# Blinker_02.net
KiCad netlist of a schematic drawn in EAGLE
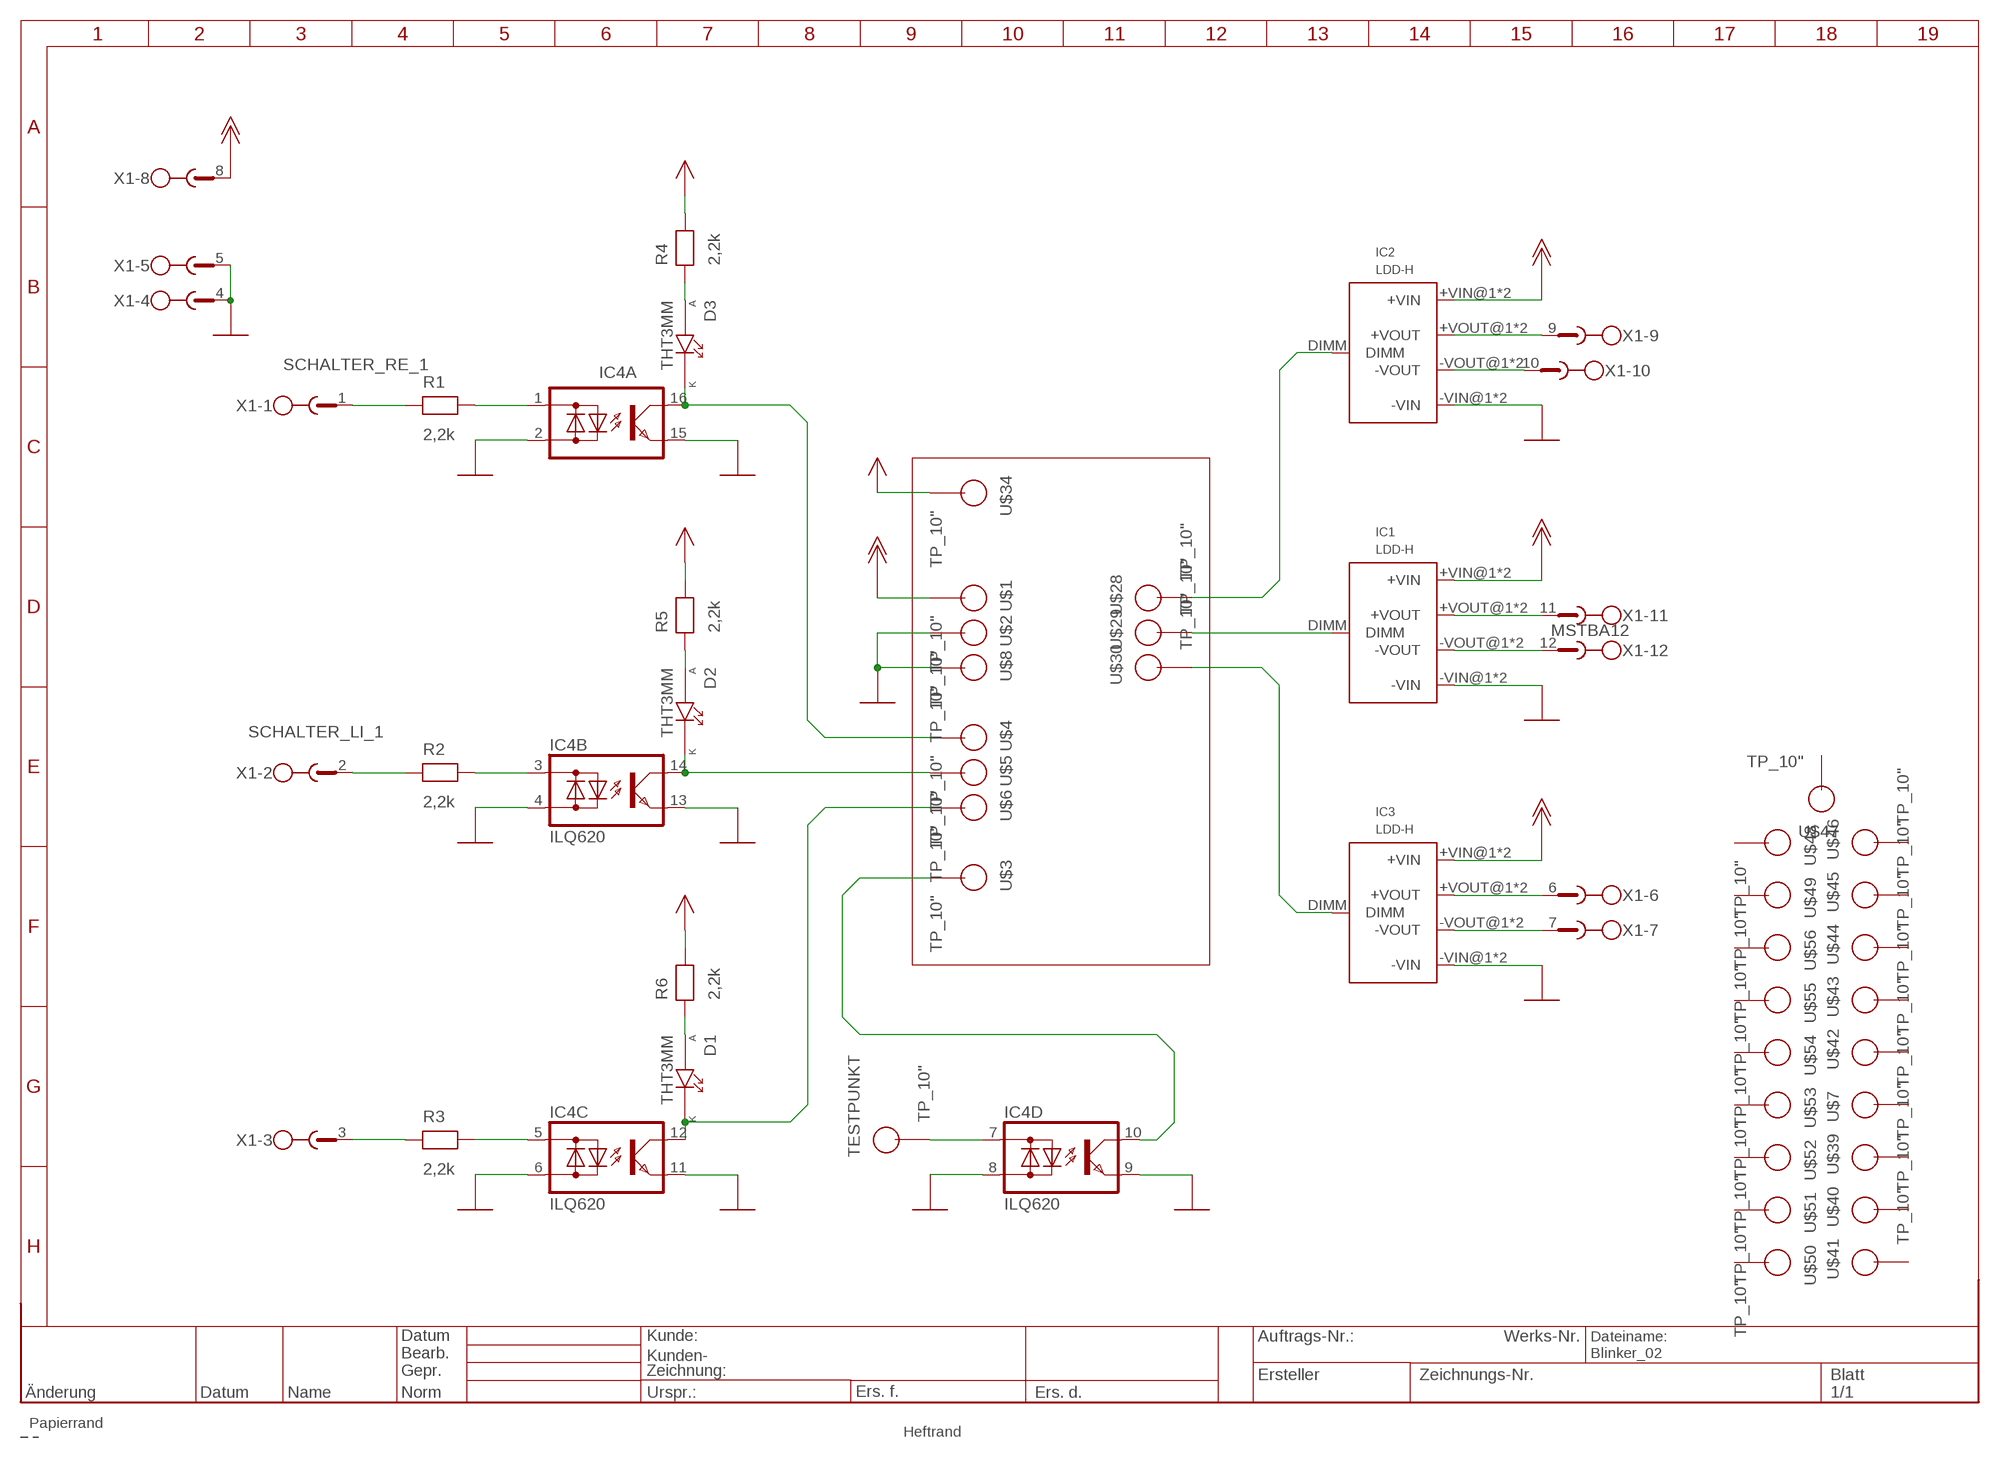
[diagram p0: schematic, sheet 1]

(export (version "E")
  (design (tool "Eeschema 10.0.6"))
  (components
    (comp (ref "D1")
      (value "THT3MM")
      (footprint "eagle-import:THT3MM")
      (libsource (lib "eagle-import") (part "THT3MM"))
    )
    (comp (ref "D2")
      (value "THT3MM")
      (footprint "eagle-import:THT3MM")
      (libsource (lib "eagle-import") (part "THT3MM"))
    )
    (comp (ref "D3")
      (value "THT3MM")
      (footprint "eagle-import:THT3MM")
      (libsource (lib "eagle-import") (part "THT3MM"))
    )
    (comp (ref "IC1")
      (value "LDD-H")
      (footprint "eagle-import:LDD-H")
      (libsource (lib "eagle-import") (part "LDD-H"))
    )
    (comp (ref "IC2")
      (value "LDD-H")
      (footprint "eagle-import:LDD-H")
      (libsource (lib "eagle-import") (part "LDD-H"))
    )
    (comp (ref "IC3")
      (value "LDD-H")
      (footprint "eagle-import:LDD-H")
      (libsource (lib "eagle-import") (part "LDD-H"))
    )
    (comp (ref "IC4")
      (value "ILQ620")
      (footprint "eagle-import:DIL16")
      (libsource (lib "eagle-import") (part "ILQ620"))
    )
    (comp (ref "R1")
      (value "2,2k")
      (footprint "eagle-import:R-10")
      (libsource (lib "eagle-import") (part "RESEU-10"))
    )
    (comp (ref "R2")
      (value "2,2k")
      (footprint "eagle-import:R-10")
      (libsource (lib "eagle-import") (part "RESEU-10"))
    )
    (comp (ref "R3")
      (value "2,2k")
      (footprint "eagle-import:R-10")
      (libsource (lib "eagle-import") (part "RESEU-10"))
    )
    (comp (ref "R4")
      (value "2,2k")
      (footprint "eagle-import:R-10")
      (libsource (lib "eagle-import") (part "RESEU-10"))
    )
    (comp (ref "R5")
      (value "2,2k")
      (footprint "eagle-import:R-10")
      (libsource (lib "eagle-import") (part "RESEU-10"))
    )
    (comp (ref "R6")
      (value "2,2k")
      (footprint "eagle-import:R-10")
      (libsource (lib "eagle-import") (part "RESEU-10"))
    )
    (comp (ref "TESTPUNKT")
      (value "TP_10\"")
      (footprint "eagle-import:TP_10")
      (libsource (lib "eagle-import") (part "TP_10{dblquote}"))
    )
    (comp (ref "U$1")
      (value "TP_10\"")
      (footprint "eagle-import:TP_10")
      (libsource (lib "eagle-import") (part "TP_10{dblquote}"))
    )
    (comp (ref "U$2")
      (value "TP_10\"")
      (footprint "eagle-import:TP_10")
      (libsource (lib "eagle-import") (part "TP_10{dblquote}"))
    )
    (comp (ref "U$3")
      (value "TP_10\"")
      (footprint "eagle-import:TP_10")
      (libsource (lib "eagle-import") (part "TP_10{dblquote}"))
    )
    (comp (ref "U$4")
      (value "TP_10\"")
      (footprint "eagle-import:TP_10")
      (libsource (lib "eagle-import") (part "TP_10{dblquote}"))
    )
    (comp (ref "U$5")
      (value "TP_10\"")
      (footprint "eagle-import:TP_10")
      (libsource (lib "eagle-import") (part "TP_10{dblquote}"))
    )
    (comp (ref "U$6")
      (value "TP_10\"")
      (footprint "eagle-import:TP_10")
      (libsource (lib "eagle-import") (part "TP_10{dblquote}"))
    )
    (comp (ref "U$7")
      (value "TP_10\"")
      (footprint "eagle-import:TP_10")
      (libsource (lib "eagle-import") (part "TP_10{dblquote}"))
    )
    (comp (ref "U$8")
      (value "TP_10\"")
      (footprint "eagle-import:TP_10")
      (libsource (lib "eagle-import") (part "TP_10{dblquote}"))
    )
    (comp (ref "U$28")
      (value "TP_10\"")
      (footprint "eagle-import:TP_10")
      (libsource (lib "eagle-import") (part "TP_10{dblquote}"))
    )
    (comp (ref "U$29")
      (value "TP_10\"")
      (footprint "eagle-import:TP_10")
      (libsource (lib "eagle-import") (part "TP_10{dblquote}"))
    )
    (comp (ref "U$30")
      (value "TP_10\"")
      (footprint "eagle-import:TP_10")
      (libsource (lib "eagle-import") (part "TP_10{dblquote}"))
    )
    (comp (ref "U$34")
      (value "TP_10\"")
      (footprint "eagle-import:TP_10")
      (libsource (lib "eagle-import") (part "TP_10{dblquote}"))
    )
    (comp (ref "U$39")
      (value "TP_10\"")
      (footprint "eagle-import:TP_10")
      (libsource (lib "eagle-import") (part "TP_10{dblquote}"))
    )
    (comp (ref "U$40")
      (value "TP_10\"")
      (footprint "eagle-import:TP_10")
      (libsource (lib "eagle-import") (part "TP_10{dblquote}"))
    )
    (comp (ref "U$41")
      (value "TP_10\"")
      (footprint "eagle-import:TP_10")
      (libsource (lib "eagle-import") (part "TP_10{dblquote}"))
    )
    (comp (ref "U$42")
      (value "TP_10\"")
      (footprint "eagle-import:TP_10")
      (libsource (lib "eagle-import") (part "TP_10{dblquote}"))
    )
    (comp (ref "U$43")
      (value "TP_10\"")
      (footprint "eagle-import:TP_10")
      (libsource (lib "eagle-import") (part "TP_10{dblquote}"))
    )
    (comp (ref "U$44")
      (value "TP_10\"")
      (footprint "eagle-import:TP_10")
      (libsource (lib "eagle-import") (part "TP_10{dblquote}"))
    )
    (comp (ref "U$45")
      (value "TP_10\"")
      (footprint "eagle-import:TP_10")
      (libsource (lib "eagle-import") (part "TP_10{dblquote}"))
    )
    (comp (ref "U$46")
      (value "TP_10\"")
      (footprint "eagle-import:TP_10")
      (libsource (lib "eagle-import") (part "TP_10{dblquote}"))
    )
    (comp (ref "U$47")
      (value "TP_10\"")
      (footprint "eagle-import:TP_10")
      (libsource (lib "eagle-import") (part "TP_10{dblquote}"))
    )
    (comp (ref "U$48")
      (value "TP_10\"")
      (footprint "eagle-import:TP_10")
      (libsource (lib "eagle-import") (part "TP_10{dblquote}"))
    )
    (comp (ref "U$49")
      (value "TP_10\"")
      (footprint "eagle-import:TP_10")
      (libsource (lib "eagle-import") (part "TP_10{dblquote}"))
    )
    (comp (ref "U$50")
      (value "TP_10\"")
      (footprint "eagle-import:TP_10")
      (libsource (lib "eagle-import") (part "TP_10{dblquote}"))
    )
    (comp (ref "U$51")
      (value "TP_10\"")
      (footprint "eagle-import:TP_10")
      (libsource (lib "eagle-import") (part "TP_10{dblquote}"))
    )
    (comp (ref "U$52")
      (value "TP_10\"")
      (footprint "eagle-import:TP_10")
      (libsource (lib "eagle-import") (part "TP_10{dblquote}"))
    )
    (comp (ref "U$53")
      (value "TP_10\"")
      (footprint "eagle-import:TP_10")
      (libsource (lib "eagle-import") (part "TP_10{dblquote}"))
    )
    (comp (ref "U$54")
      (value "TP_10\"")
      (footprint "eagle-import:TP_10")
      (libsource (lib "eagle-import") (part "TP_10{dblquote}"))
    )
    (comp (ref "U$55")
      (value "TP_10\"")
      (footprint "eagle-import:TP_10")
      (libsource (lib "eagle-import") (part "TP_10{dblquote}"))
    )
    (comp (ref "U$56")
      (value "TP_10\"")
      (footprint "eagle-import:TP_10")
      (libsource (lib "eagle-import") (part "TP_10{dblquote}"))
    )
    (comp (ref "X1")
      (value "MSTBA12")
      (footprint "eagle-import:MSTBA12")
      (fields (field (name "MPN") "1757349"))
      (libsource (lib "eagle-import") (part "MSTBA12"))
    )
  )
  (nets
    (net (code "1") (name "+5V") (class "Default")
      (node (ref "R4") (pin "2") (pinfunction "2_2") (pintype "passive"))
      (node (ref "R5") (pin "2") (pinfunction "2_2") (pintype "passive"))
      (node (ref "R6") (pin "2") (pinfunction "2_2") (pintype "passive"))
      (node (ref "U$34") (pin "P$1") (pinfunction "TP_13_P$1") (pintype "bidirectional"))
    )
    (net (code "2") (name "+12V") (class "Default")
      (node (ref "IC1") (pin "+VIN@1") (pinfunction "+VIN_+VIN@1") (pintype "power_in"))
      (node (ref "IC1") (pin "+VIN@2") (pinfunction "+VIN_+VIN@2") (pintype "power_in"))
      (node (ref "IC2") (pin "+VIN@1") (pinfunction "+VIN_+VIN@1") (pintype "power_in"))
      (node (ref "IC2") (pin "+VIN@2") (pinfunction "+VIN_+VIN@2") (pintype "power_in"))
      (node (ref "IC3") (pin "+VIN@1") (pinfunction "+VIN_+VIN@1") (pintype "power_in"))
      (node (ref "IC3") (pin "+VIN@2") (pinfunction "+VIN_+VIN@2") (pintype "power_in"))
      (node (ref "U$1") (pin "P$1") (pinfunction "TP_13_P$1") (pintype "bidirectional"))
      (node (ref "X1") (pin "8") (pinfunction "1_8") (pintype "passive"))
    )
    (net (code "3") (name "/SCHALTER_LI_1") (class "Default")
      (node (ref "R2") (pin "1") (pinfunction "1_1") (pintype "passive"))
      (node (ref "X1") (pin "2") (pinfunction "1_2") (pintype "passive"))
    )
    (net (code "4") (name "/SCHALTER_RE_1") (class "Default")
      (node (ref "R1") (pin "1") (pinfunction "1_1") (pintype "passive"))
      (node (ref "X1") (pin "1") (pinfunction "1_1") (pintype "passive"))
    )
    (net (code "5") (name "GND") (class "Default")
      (node (ref "IC1") (pin "-VIN@1") (pinfunction "-VIN_-VIN@1") (pintype "power_in"))
      (node (ref "IC1") (pin "-VIN@2") (pinfunction "-VIN_-VIN@2") (pintype "power_in"))
      (node (ref "IC2") (pin "-VIN@1") (pinfunction "-VIN_-VIN@1") (pintype "power_in"))
      (node (ref "IC2") (pin "-VIN@2") (pinfunction "-VIN_-VIN@2") (pintype "power_in"))
      (node (ref "IC3") (pin "-VIN@1") (pinfunction "-VIN_-VIN@1") (pintype "power_in"))
      (node (ref "IC3") (pin "-VIN@2") (pinfunction "-VIN_-VIN@2") (pintype "power_in"))
      (node (ref "IC4") (pin "11") (pinfunction "E_11") (pintype "passive"))
      (node (ref "IC4") (pin "13") (pinfunction "E_13") (pintype "passive"))
      (node (ref "IC4") (pin "15") (pinfunction "E_15") (pintype "passive"))
      (node (ref "IC4") (pin "2") (pinfunction "AC2_2") (pintype "passive"))
      (node (ref "IC4") (pin "4") (pinfunction "AC2_4") (pintype "passive"))
      (node (ref "IC4") (pin "6") (pinfunction "AC2_6") (pintype "passive"))
      (node (ref "IC4") (pin "8") (pinfunction "AC2_8") (pintype "passive"))
      (node (ref "IC4") (pin "9") (pinfunction "E_9") (pintype "passive"))
      (node (ref "U$2") (pin "P$1") (pinfunction "TP_13_P$1") (pintype "bidirectional"))
      (node (ref "U$8") (pin "P$1") (pinfunction "TP_13_P$1") (pintype "bidirectional"))
      (node (ref "X1") (pin "4") (pinfunction "1_4") (pintype "passive"))
      (node (ref "X1") (pin "5") (pinfunction "1_5") (pintype "passive"))
    )
    (net (code "6") (name "Net-(D1-P1A)") (class "Default")
      (node (ref "D1") (pin "A") (pinfunction "P1A_A") (pintype "bidirectional"))
      (node (ref "R6") (pin "1") (pinfunction "1_1") (pintype "passive"))
    )
    (net (code "7") (name "Net-(D1-P2K)") (class "Default")
      (node (ref "D1") (pin "K") (pinfunction "P2K_K") (pintype "bidirectional"))
      (node (ref "IC4") (pin "12") (pinfunction "C_12") (pintype "passive"))
      (node (ref "U$6") (pin "P$1") (pinfunction "TP_13_P$1") (pintype "bidirectional"))
    )
    (net (code "8") (name "Net-(D2-P1A)") (class "Default")
      (node (ref "D2") (pin "A") (pinfunction "P1A_A") (pintype "bidirectional"))
      (node (ref "R5") (pin "1") (pinfunction "1_1") (pintype "passive"))
    )
    (net (code "9") (name "Net-(D2-P2K)") (class "Default")
      (node (ref "D2") (pin "K") (pinfunction "P2K_K") (pintype "bidirectional"))
      (node (ref "IC4") (pin "14") (pinfunction "C_14") (pintype "passive"))
      (node (ref "U$5") (pin "P$1") (pinfunction "TP_13_P$1") (pintype "bidirectional"))
    )
    (net (code "10") (name "Net-(D3-P1A)") (class "Default")
      (node (ref "D3") (pin "A") (pinfunction "P1A_A") (pintype "bidirectional"))
      (node (ref "R4") (pin "1") (pinfunction "1_1") (pintype "passive"))
    )
    (net (code "11") (name "Net-(D3-P2K)") (class "Default")
      (node (ref "D3") (pin "K") (pinfunction "P2K_K") (pintype "bidirectional"))
      (node (ref "IC4") (pin "16") (pinfunction "C_16") (pintype "passive"))
      (node (ref "U$4") (pin "P$1") (pinfunction "TP_13_P$1") (pintype "bidirectional"))
    )
    (net (code "12") (name "Net-(IC4A-AC1)") (class "Default")
      (node (ref "IC4") (pin "1") (pinfunction "AC1_1") (pintype "passive"))
      (node (ref "R1") (pin "2") (pinfunction "2_2") (pintype "passive"))
    )
    (net (code "13") (name "Net-(IC4B-AC1)") (class "Default")
      (node (ref "IC4") (pin "3") (pinfunction "AC1_3") (pintype "passive"))
      (node (ref "R2") (pin "2") (pinfunction "2_2") (pintype "passive"))
    )
    (net (code "14") (name "Net-(IC4C-AC1)") (class "Default")
      (node (ref "IC4") (pin "5") (pinfunction "AC1_5") (pintype "passive"))
      (node (ref "R3") (pin "2") (pinfunction "2_2") (pintype "passive"))
    )
    (net (code "15") (name "Net-(IC4D-AC1)") (class "Default")
      (node (ref "IC4") (pin "7") (pinfunction "AC1_7") (pintype "passive"))
      (node (ref "TESTPUNKT") (pin "P$1") (pinfunction "TP_13_P$1") (pintype "bidirectional"))
    )
    (net (code "16") (name "Net-(IC4D-C)") (class "Default")
      (node (ref "IC4") (pin "10") (pinfunction "C_10") (pintype "passive"))
      (node (ref "U$3") (pin "P$1") (pinfunction "TP_13_P$1") (pintype "bidirectional"))
    )
    (net (code "17") (name "Net-(U$28-TP_13)") (class "Default")
      (node (ref "IC2") (pin "DIMM") (pinfunction "DIMM_DIMM") (pintype "input"))
      (node (ref "U$28") (pin "P$1") (pinfunction "TP_13_P$1") (pintype "bidirectional"))
    )
    (net (code "18") (name "Net-(U$29-TP_13)") (class "Default")
      (node (ref "IC1") (pin "DIMM") (pinfunction "DIMM_DIMM") (pintype "input"))
      (node (ref "U$29") (pin "P$1") (pinfunction "TP_13_P$1") (pintype "bidirectional"))
    )
    (net (code "19") (name "Net-(U$30-TP_13)") (class "Default")
      (node (ref "IC3") (pin "DIMM") (pinfunction "DIMM_DIMM") (pintype "input"))
      (node (ref "U$30") (pin "P$1") (pinfunction "TP_13_P$1") (pintype "bidirectional"))
    )
    (net (code "20") (name "Net-(X1B-1)") (class "Default")
      (node (ref "IC2") (pin "-VOUT@1") (pinfunction "-VOUT_-VOUT@1") (pintype "output"))
      (node (ref "IC2") (pin "-VOUT@2") (pinfunction "-VOUT_-VOUT@2") (pintype "output"))
      (node (ref "X1") (pin "10") (pinfunction "1_10") (pintype "passive"))
    )
    (net (code "21") (name "Net-(X1C-1)") (class "Default")
      (node (ref "IC1") (pin "+VOUT@1") (pinfunction "+VOUT_+VOUT@1") (pintype "output"))
      (node (ref "IC1") (pin "+VOUT@2") (pinfunction "+VOUT_+VOUT@2") (pintype "output"))
      (node (ref "X1") (pin "11") (pinfunction "1_11") (pintype "passive"))
    )
    (net (code "22") (name "Net-(X1D-1)") (class "Default")
      (node (ref "IC1") (pin "-VOUT@1") (pinfunction "-VOUT_-VOUT@1") (pintype "output"))
      (node (ref "IC1") (pin "-VOUT@2") (pinfunction "-VOUT_-VOUT@2") (pintype "output"))
      (node (ref "X1") (pin "12") (pinfunction "1_12") (pintype "passive"))
    )
    (net (code "23") (name "Net-(X1F-1)") (class "Default")
      (node (ref "R3") (pin "1") (pinfunction "1_1") (pintype "passive"))
      (node (ref "X1") (pin "3") (pinfunction "1_3") (pintype "passive"))
    )
    (net (code "24") (name "Net-(X1I-1)") (class "Default")
      (node (ref "IC3") (pin "+VOUT@1") (pinfunction "+VOUT_+VOUT@1") (pintype "output"))
      (node (ref "IC3") (pin "+VOUT@2") (pinfunction "+VOUT_+VOUT@2") (pintype "output"))
      (node (ref "X1") (pin "6") (pinfunction "1_6") (pintype "passive"))
    )
    (net (code "25") (name "Net-(X1J-1)") (class "Default")
      (node (ref "IC3") (pin "-VOUT@1") (pinfunction "-VOUT_-VOUT@1") (pintype "output"))
      (node (ref "IC3") (pin "-VOUT@2") (pinfunction "-VOUT_-VOUT@2") (pintype "output"))
      (node (ref "X1") (pin "7") (pinfunction "1_7") (pintype "passive"))
    )
    (net (code "26") (name "Net-(X1L-1)") (class "Default")
      (node (ref "IC2") (pin "+VOUT@1") (pinfunction "+VOUT_+VOUT@1") (pintype "output"))
      (node (ref "IC2") (pin "+VOUT@2") (pinfunction "+VOUT_+VOUT@2") (pintype "output"))
      (node (ref "X1") (pin "9") (pinfunction "1_9") (pintype "passive"))
    )
    (net (code "27") (name "unconnected-(U$7-TP_13-PadP$1)") (class "Default")
      (node (ref "U$7") (pin "P$1") (pinfunction "TP_13_P$1") (pintype "bidirectional"))
    )
    (net (code "28") (name "unconnected-(U$39-TP_13-PadP$1)") (class "Default")
      (node (ref "U$39") (pin "P$1") (pinfunction "TP_13_P$1") (pintype "bidirectional"))
    )
    (net (code "29") (name "unconnected-(U$40-TP_13-PadP$1)") (class "Default")
      (node (ref "U$40") (pin "P$1") (pinfunction "TP_13_P$1") (pintype "bidirectional"))
    )
    (net (code "30") (name "unconnected-(U$41-TP_13-PadP$1)") (class "Default")
      (node (ref "U$41") (pin "P$1") (pinfunction "TP_13_P$1") (pintype "bidirectional"))
    )
    (net (code "31") (name "unconnected-(U$42-TP_13-PadP$1)") (class "Default")
      (node (ref "U$42") (pin "P$1") (pinfunction "TP_13_P$1") (pintype "bidirectional"))
    )
    (net (code "32") (name "unconnected-(U$43-TP_13-PadP$1)") (class "Default")
      (node (ref "U$43") (pin "P$1") (pinfunction "TP_13_P$1") (pintype "bidirectional"))
    )
    (net (code "33") (name "unconnected-(U$44-TP_13-PadP$1)") (class "Default")
      (node (ref "U$44") (pin "P$1") (pinfunction "TP_13_P$1") (pintype "bidirectional"))
    )
    (net (code "34") (name "unconnected-(U$45-TP_13-PadP$1)") (class "Default")
      (node (ref "U$45") (pin "P$1") (pinfunction "TP_13_P$1") (pintype "bidirectional"))
    )
    (net (code "35") (name "unconnected-(U$46-TP_13-PadP$1)") (class "Default")
      (node (ref "U$46") (pin "P$1") (pinfunction "TP_13_P$1") (pintype "bidirectional"))
    )
    (net (code "36") (name "unconnected-(U$47-TP_13-PadP$1)") (class "Default")
      (node (ref "U$47") (pin "P$1") (pinfunction "TP_13_P$1") (pintype "bidirectional"))
    )
    (net (code "37") (name "unconnected-(U$48-TP_13-PadP$1)") (class "Default")
      (node (ref "U$48") (pin "P$1") (pinfunction "TP_13_P$1") (pintype "bidirectional"))
    )
    (net (code "38") (name "unconnected-(U$49-TP_13-PadP$1)") (class "Default")
      (node (ref "U$49") (pin "P$1") (pinfunction "TP_13_P$1") (pintype "bidirectional"))
    )
    (net (code "39") (name "unconnected-(U$50-TP_13-PadP$1)") (class "Default")
      (node (ref "U$50") (pin "P$1") (pinfunction "TP_13_P$1") (pintype "bidirectional"))
    )
    (net (code "40") (name "unconnected-(U$51-TP_13-PadP$1)") (class "Default")
      (node (ref "U$51") (pin "P$1") (pinfunction "TP_13_P$1") (pintype "bidirectional"))
    )
    (net (code "41") (name "unconnected-(U$52-TP_13-PadP$1)") (class "Default")
      (node (ref "U$52") (pin "P$1") (pinfunction "TP_13_P$1") (pintype "bidirectional"))
    )
    (net (code "42") (name "unconnected-(U$53-TP_13-PadP$1)") (class "Default")
      (node (ref "U$53") (pin "P$1") (pinfunction "TP_13_P$1") (pintype "bidirectional"))
    )
    (net (code "43") (name "unconnected-(U$54-TP_13-PadP$1)") (class "Default")
      (node (ref "U$54") (pin "P$1") (pinfunction "TP_13_P$1") (pintype "bidirectional"))
    )
    (net (code "44") (name "unconnected-(U$55-TP_13-PadP$1)") (class "Default")
      (node (ref "U$55") (pin "P$1") (pinfunction "TP_13_P$1") (pintype "bidirectional"))
    )
    (net (code "45") (name "unconnected-(U$56-TP_13-PadP$1)") (class "Default")
      (node (ref "U$56") (pin "P$1") (pinfunction "TP_13_P$1") (pintype "bidirectional"))
    )
  )
)
